# MCU.net
KiCad netlist of a schematic drawn in Altium Designer
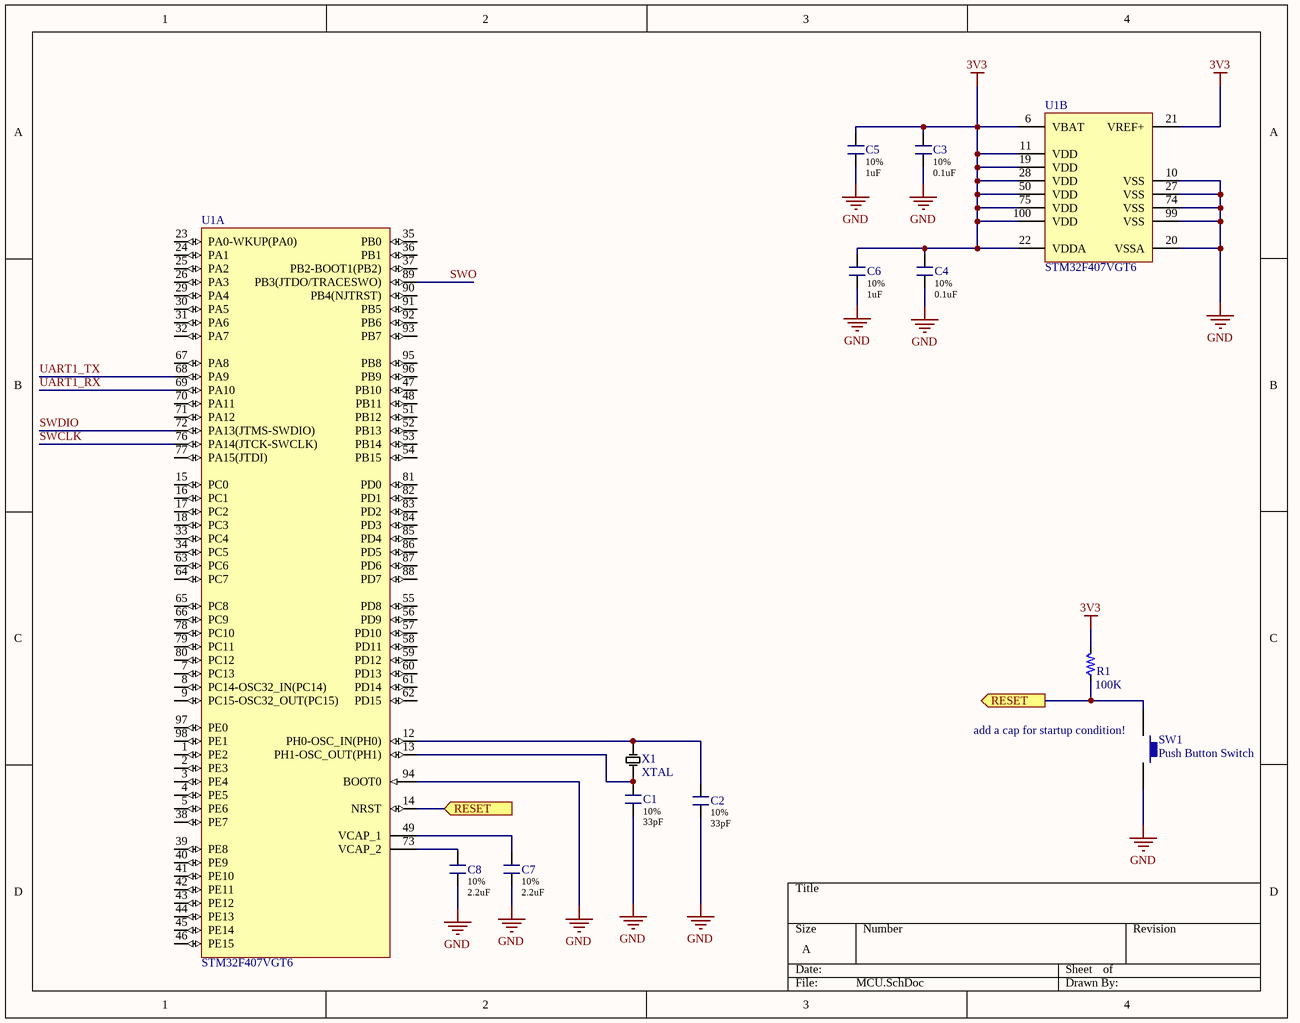
[diagram p0: MCU.SchDoc]

(export (version "E")
  (design (tool "Eeschema 10.0.6"))
  (components
    (comp (ref "C1")
      (value "SCH_GENERIC_CAPACITOR_0603")
      (footprint "PCB_GENERIC_SMD_0603")
      (description "Generic SMD capacitor 0603")
      (fields (field (name "TOLERANCE") "10%") (field (name "CAPACITANCE") "33pF"))
      (libsource (lib "Generic 0603 Capacitor") (part "SCH_GENERIC_CAPACITOR_0603"))
    )
    (comp (ref "C2")
      (value "SCH_GENERIC_CAPACITOR_0603")
      (footprint "PCB_GENERIC_SMD_0603")
      (description "Generic SMD capacitor 0603")
      (fields (field (name "TOLERANCE") "10%") (field (name "CAPACITANCE") "33pF"))
      (libsource (lib "Generic 0603 Capacitor") (part "SCH_GENERIC_CAPACITOR_0603"))
    )
    (comp (ref "C3")
      (value "SCH_GENERIC_CAPACITOR_0603")
      (footprint "PCB_GENERIC_SMD_0603")
      (description "Generic SMD capacitor 0603")
      (fields (field (name "TOLERANCE") "10%") (field (name "CAPACITANCE") "0.1uF"))
      (libsource (lib "Generic 0603 Capacitor") (part "SCH_GENERIC_CAPACITOR_0603"))
    )
    (comp (ref "C4")
      (value "SCH_GENERIC_CAPACITOR_0603")
      (footprint "PCB_GENERIC_SMD_0603")
      (description "Generic SMD capacitor 0603")
      (fields (field (name "TOLERANCE") "10%") (field (name "CAPACITANCE") "0.1uF"))
      (libsource (lib "Generic 0603 Capacitor") (part "SCH_GENERIC_CAPACITOR_0603"))
    )
    (comp (ref "C5")
      (value "SCH_GENERIC_CAPACITOR_0603")
      (footprint "PCB_GENERIC_SMD_0603")
      (description "Generic SMD capacitor 0603")
      (fields (field (name "TOLERANCE") "10%") (field (name "CAPACITANCE") "1uF"))
      (libsource (lib "Generic 0603 Capacitor") (part "SCH_GENERIC_CAPACITOR_0603"))
    )
    (comp (ref "C6")
      (value "SCH_GENERIC_CAPACITOR_0603")
      (footprint "PCB_GENERIC_SMD_0603")
      (description "Generic SMD capacitor 0603")
      (fields (field (name "TOLERANCE") "10%") (field (name "CAPACITANCE") "1uF"))
      (libsource (lib "Generic 0603 Capacitor") (part "SCH_GENERIC_CAPACITOR_0603"))
    )
    (comp (ref "C7")
      (value "SCH_GENERIC_CAPACITOR_0603")
      (footprint "PCB_GENERIC_SMD_0603")
      (description "Generic SMD capacitor 0603")
      (fields (field (name "TOLERANCE") "10%") (field (name "CAPACITANCE") "2.2uF"))
      (libsource (lib "Generic 0603 Capacitor") (part "SCH_GENERIC_CAPACITOR_0603"))
    )
    (comp (ref "C8")
      (value "SCH_GENERIC_CAPACITOR_0603")
      (footprint "PCB_GENERIC_SMD_0603")
      (description "Generic SMD capacitor 0603")
      (fields (field (name "TOLERANCE") "10%") (field (name "CAPACITANCE") "2.2uF"))
      (libsource (lib "Generic 0603 Capacitor") (part "SCH_GENERIC_CAPACITOR_0603"))
    )
    (comp (ref "R1")
      (value "SCH_GENERIC_RESISTOR_0603")
      (footprint "PCB_GENERIC_SMD_0603")
      (description "Generic SMD resistor 0603")
      (fields (field (name "RESISTANCE") "100K"))
      (libsource (lib "Generic 0603 Resistor") (part "SCH_GENERIC_RESISTOR_0603"))
    )
    (comp (ref "SW1")
      (value "Push Button Switch")
      (footprint "Push Button Switch")
      (libsource (lib "Surface Mount Push Button Switch") (part "PushButtonSwitch"))
    )
    (comp (ref "U1")
      (value "STM32F407VGT6")
      (footprint "STM-LQFP100_N")
      (fields (field (name "MANUFACTURER") "STMicroelectronics"))
      (libsource (lib "STMicroelectronics STM32 F4") (part "STM32F407VGT6"))
    )
    (comp (ref "X1")
      (value "XTAL")
      (footprint "CRYSTAL_8MHZ")
      (libsource (lib "Foxslf 8MHz Crystal") (part "Crystal"))
    )
  )
  (nets
    (net (code "1") (name "/RESET") (class "Default")
      (node (ref "R1") (pin "1") (pinfunction "1_1") (pintype "passive"))
      (node (ref "SW1") (pin "1") (pinfunction "1_1") (pintype "passive"))
      (node (ref "U1") (pin "14") (pinfunction "NRST_14") (pintype "bidirectional"))
    )
    (net (code "2") (name "/SWCLK") (class "Default")
      (node (ref "U1") (pin "76") (pinfunction "PA14(JTCK-SWCLK)_76") (pintype "bidirectional"))
    )
    (net (code "3") (name "/SWDIO") (class "Default")
      (node (ref "U1") (pin "72") (pinfunction "PA13(JTMS-SWDIO)_72") (pintype "bidirectional"))
    )
    (net (code "4") (name "/SWO") (class "Default")
      (node (ref "U1") (pin "89") (pinfunction "PB3(JTDO/TRACESWO)_89") (pintype "bidirectional"))
    )
    (net (code "5") (name "/UART1_RX") (class "Default")
      (node (ref "U1") (pin "69") (pinfunction "PA10_69") (pintype "bidirectional"))
    )
    (net (code "6") (name "/UART1_TX") (class "Default")
      (node (ref "U1") (pin "68") (pinfunction "PA9_68") (pintype "bidirectional"))
    )
    (net (code "7") (name "3V3") (class "Default")
      (node (ref "C3") (pin "2") (pinfunction "2_2") (pintype "passive"))
      (node (ref "C4") (pin "2") (pinfunction "2_2") (pintype "passive"))
      (node (ref "C5") (pin "2") (pinfunction "2_2") (pintype "passive"))
      (node (ref "C6") (pin "2") (pinfunction "2_2") (pintype "passive"))
      (node (ref "R1") (pin "2") (pinfunction "2_2") (pintype "passive"))
      (node (ref "U1") (pin "100") (pinfunction "VDD_100") (pintype "power_in"))
      (node (ref "U1") (pin "11") (pinfunction "VDD_11") (pintype "power_in"))
      (node (ref "U1") (pin "19") (pinfunction "VDD_19") (pintype "power_in"))
      (node (ref "U1") (pin "21") (pinfunction "VREF+_21") (pintype "power_in"))
      (node (ref "U1") (pin "22") (pinfunction "VDDA_22") (pintype "power_in"))
      (node (ref "U1") (pin "28") (pinfunction "VDD_28") (pintype "power_in"))
      (node (ref "U1") (pin "50") (pinfunction "VDD_50") (pintype "power_in"))
      (node (ref "U1") (pin "6") (pinfunction "VBAT_6") (pintype "power_in"))
      (node (ref "U1") (pin "75") (pinfunction "VDD_75") (pintype "power_in"))
    )
    (net (code "8") (name "GND") (class "Default")
      (node (ref "C1") (pin "1") (pinfunction "1_1") (pintype "passive"))
      (node (ref "C2") (pin "1") (pinfunction "1_1") (pintype "passive"))
      (node (ref "C3") (pin "1") (pinfunction "1_1") (pintype "passive"))
      (node (ref "C4") (pin "1") (pinfunction "1_1") (pintype "passive"))
      (node (ref "C5") (pin "1") (pinfunction "1_1") (pintype "passive"))
      (node (ref "C6") (pin "1") (pinfunction "1_1") (pintype "passive"))
      (node (ref "C7") (pin "1") (pinfunction "1_1") (pintype "passive"))
      (node (ref "C8") (pin "1") (pinfunction "1_1") (pintype "passive"))
      (node (ref "SW1") (pin "2") (pinfunction "2_2") (pintype "passive"))
      (node (ref "U1") (pin "10") (pinfunction "VSS_10") (pintype "power_in"))
      (node (ref "U1") (pin "20") (pinfunction "VSSA_20") (pintype "power_in"))
      (node (ref "U1") (pin "27") (pinfunction "VSS_27") (pintype "power_in"))
      (node (ref "U1") (pin "74") (pinfunction "VSS_74") (pintype "power_in"))
      (node (ref "U1") (pin "94") (pinfunction "BOOT0_94") (pintype "input"))
      (node (ref "U1") (pin "99") (pinfunction "VSS_99") (pintype "power_in"))
    )
    (net (code "9") (name "Net-(U1A-PH0-OSC_IN(PH0))") (class "Default")
      (node (ref "C2") (pin "2") (pinfunction "2_2") (pintype "passive"))
      (node (ref "U1") (pin "12") (pinfunction "PH0-OSC_IN(PH0)_12") (pintype "bidirectional"))
      (node (ref "X1") (pin "2") (pintype "passive"))
    )
    (net (code "10") (name "Net-(U1A-PH1-OSC_OUT(PH1))") (class "Default")
      (node (ref "C1") (pin "2") (pinfunction "2_2") (pintype "passive"))
      (node (ref "U1") (pin "13") (pinfunction "PH1-OSC_OUT(PH1)_13") (pintype "bidirectional"))
      (node (ref "X1") (pin "1") (pintype "passive"))
    )
    (net (code "11") (name "Net-(U1A-VCAP_1)") (class "Default")
      (node (ref "C7") (pin "2") (pinfunction "2_2") (pintype "passive"))
      (node (ref "U1") (pin "49") (pinfunction "VCAP_1_49") (pintype "power_in"))
    )
    (net (code "12") (name "Net-(U1A-VCAP_2)") (class "Default")
      (node (ref "C8") (pin "2") (pinfunction "2_2") (pintype "passive"))
      (node (ref "U1") (pin "73") (pinfunction "VCAP_2_73") (pintype "power_in"))
    )
    (net (code "13") (name "unconnected-(U1A-PA0-WKUP(PA0)-Pad23)") (class "Default")
      (node (ref "U1") (pin "23") (pinfunction "PA0-WKUP(PA0)_23") (pintype "bidirectional"))
    )
    (net (code "14") (name "unconnected-(U1A-PA1-Pad24)") (class "Default")
      (node (ref "U1") (pin "24") (pinfunction "PA1_24") (pintype "bidirectional"))
    )
    (net (code "15") (name "unconnected-(U1A-PA2-Pad25)") (class "Default")
      (node (ref "U1") (pin "25") (pinfunction "PA2_25") (pintype "bidirectional"))
    )
    (net (code "16") (name "unconnected-(U1A-PA3-Pad26)") (class "Default")
      (node (ref "U1") (pin "26") (pinfunction "PA3_26") (pintype "bidirectional"))
    )
    (net (code "17") (name "unconnected-(U1A-PA4-Pad29)") (class "Default")
      (node (ref "U1") (pin "29") (pinfunction "PA4_29") (pintype "bidirectional"))
    )
    (net (code "18") (name "unconnected-(U1A-PA5-Pad30)") (class "Default")
      (node (ref "U1") (pin "30") (pinfunction "PA5_30") (pintype "bidirectional"))
    )
    (net (code "19") (name "unconnected-(U1A-PA6-Pad31)") (class "Default")
      (node (ref "U1") (pin "31") (pinfunction "PA6_31") (pintype "bidirectional"))
    )
    (net (code "20") (name "unconnected-(U1A-PA7-Pad32)") (class "Default")
      (node (ref "U1") (pin "32") (pinfunction "PA7_32") (pintype "bidirectional"))
    )
    (net (code "21") (name "unconnected-(U1A-PA8-Pad67)") (class "Default")
      (node (ref "U1") (pin "67") (pinfunction "PA8_67") (pintype "bidirectional"))
    )
    (net (code "22") (name "unconnected-(U1A-PA11-Pad70)") (class "Default")
      (node (ref "U1") (pin "70") (pinfunction "PA11_70") (pintype "bidirectional"))
    )
    (net (code "23") (name "unconnected-(U1A-PA12-Pad71)") (class "Default")
      (node (ref "U1") (pin "71") (pinfunction "PA12_71") (pintype "bidirectional"))
    )
    (net (code "24") (name "unconnected-(U1A-PA15(JTDI)-Pad77)") (class "Default")
      (node (ref "U1") (pin "77") (pinfunction "PA15(JTDI)_77") (pintype "bidirectional"))
    )
    (net (code "25") (name "unconnected-(U1A-PB0-Pad35)") (class "Default")
      (node (ref "U1") (pin "35") (pinfunction "PB0_35") (pintype "bidirectional"))
    )
    (net (code "26") (name "unconnected-(U1A-PB1-Pad36)") (class "Default")
      (node (ref "U1") (pin "36") (pinfunction "PB1_36") (pintype "bidirectional"))
    )
    (net (code "27") (name "unconnected-(U1A-PB2-BOOT1(PB2)-Pad37)") (class "Default")
      (node (ref "U1") (pin "37") (pinfunction "PB2-BOOT1(PB2)_37") (pintype "bidirectional"))
    )
    (net (code "28") (name "unconnected-(U1A-PB4(NJTRST)-Pad90)") (class "Default")
      (node (ref "U1") (pin "90") (pinfunction "PB4(NJTRST)_90") (pintype "bidirectional"))
    )
    (net (code "29") (name "unconnected-(U1A-PB5-Pad91)") (class "Default")
      (node (ref "U1") (pin "91") (pinfunction "PB5_91") (pintype "bidirectional"))
    )
    (net (code "30") (name "unconnected-(U1A-PB6-Pad92)") (class "Default")
      (node (ref "U1") (pin "92") (pinfunction "PB6_92") (pintype "bidirectional"))
    )
    (net (code "31") (name "unconnected-(U1A-PB7-Pad93)") (class "Default")
      (node (ref "U1") (pin "93") (pinfunction "PB7_93") (pintype "bidirectional"))
    )
    (net (code "32") (name "unconnected-(U1A-PB8-Pad95)") (class "Default")
      (node (ref "U1") (pin "95") (pinfunction "PB8_95") (pintype "bidirectional"))
    )
    (net (code "33") (name "unconnected-(U1A-PB9-Pad96)") (class "Default")
      (node (ref "U1") (pin "96") (pinfunction "PB9_96") (pintype "bidirectional"))
    )
    (net (code "34") (name "unconnected-(U1A-PB10-Pad47)") (class "Default")
      (node (ref "U1") (pin "47") (pinfunction "PB10_47") (pintype "bidirectional"))
    )
    (net (code "35") (name "unconnected-(U1A-PB11-Pad48)") (class "Default")
      (node (ref "U1") (pin "48") (pinfunction "PB11_48") (pintype "bidirectional"))
    )
    (net (code "36") (name "unconnected-(U1A-PB12-Pad51)") (class "Default")
      (node (ref "U1") (pin "51") (pinfunction "PB12_51") (pintype "bidirectional"))
    )
    (net (code "37") (name "unconnected-(U1A-PB13-Pad52)") (class "Default")
      (node (ref "U1") (pin "52") (pinfunction "PB13_52") (pintype "bidirectional"))
    )
    (net (code "38") (name "unconnected-(U1A-PB14-Pad53)") (class "Default")
      (node (ref "U1") (pin "53") (pinfunction "PB14_53") (pintype "bidirectional"))
    )
    (net (code "39") (name "unconnected-(U1A-PB15-Pad54)") (class "Default")
      (node (ref "U1") (pin "54") (pinfunction "PB15_54") (pintype "bidirectional"))
    )
    (net (code "40") (name "unconnected-(U1A-PC0-Pad15)") (class "Default")
      (node (ref "U1") (pin "15") (pinfunction "PC0_15") (pintype "bidirectional"))
    )
    (net (code "41") (name "unconnected-(U1A-PC1-Pad16)") (class "Default")
      (node (ref "U1") (pin "16") (pinfunction "PC1_16") (pintype "bidirectional"))
    )
    (net (code "42") (name "unconnected-(U1A-PC2-Pad17)") (class "Default")
      (node (ref "U1") (pin "17") (pinfunction "PC2_17") (pintype "bidirectional"))
    )
    (net (code "43") (name "unconnected-(U1A-PC3-Pad18)") (class "Default")
      (node (ref "U1") (pin "18") (pinfunction "PC3_18") (pintype "bidirectional"))
    )
    (net (code "44") (name "unconnected-(U1A-PC4-Pad33)") (class "Default")
      (node (ref "U1") (pin "33") (pinfunction "PC4_33") (pintype "bidirectional"))
    )
    (net (code "45") (name "unconnected-(U1A-PC5-Pad34)") (class "Default")
      (node (ref "U1") (pin "34") (pinfunction "PC5_34") (pintype "bidirectional"))
    )
    (net (code "46") (name "unconnected-(U1A-PC6-Pad63)") (class "Default")
      (node (ref "U1") (pin "63") (pinfunction "PC6_63") (pintype "bidirectional"))
    )
    (net (code "47") (name "unconnected-(U1A-PC7-Pad64)") (class "Default")
      (node (ref "U1") (pin "64") (pinfunction "PC7_64") (pintype "bidirectional"))
    )
    (net (code "48") (name "unconnected-(U1A-PC8-Pad65)") (class "Default")
      (node (ref "U1") (pin "65") (pinfunction "PC8_65") (pintype "bidirectional"))
    )
    (net (code "49") (name "unconnected-(U1A-PC9-Pad66)") (class "Default")
      (node (ref "U1") (pin "66") (pinfunction "PC9_66") (pintype "bidirectional"))
    )
    (net (code "50") (name "unconnected-(U1A-PC10-Pad78)") (class "Default")
      (node (ref "U1") (pin "78") (pinfunction "PC10_78") (pintype "bidirectional"))
    )
    (net (code "51") (name "unconnected-(U1A-PC11-Pad79)") (class "Default")
      (node (ref "U1") (pin "79") (pinfunction "PC11_79") (pintype "bidirectional"))
    )
    (net (code "52") (name "unconnected-(U1A-PC12-Pad80)") (class "Default")
      (node (ref "U1") (pin "80") (pinfunction "PC12_80") (pintype "bidirectional"))
    )
    (net (code "53") (name "unconnected-(U1A-PC13-Pad7)") (class "Default")
      (node (ref "U1") (pin "7") (pinfunction "PC13_7") (pintype "bidirectional"))
    )
    (net (code "54") (name "unconnected-(U1A-PC14-OSC32_IN(PC14)-Pad8)") (class "Default")
      (node (ref "U1") (pin "8") (pinfunction "PC14-OSC32_IN(PC14)_8") (pintype "bidirectional"))
    )
    (net (code "55") (name "unconnected-(U1A-PC15-OSC32_OUT(PC15)-Pad9)") (class "Default")
      (node (ref "U1") (pin "9") (pinfunction "PC15-OSC32_OUT(PC15)_9") (pintype "bidirectional"))
    )
    (net (code "56") (name "unconnected-(U1A-PD0-Pad81)") (class "Default")
      (node (ref "U1") (pin "81") (pinfunction "PD0_81") (pintype "bidirectional"))
    )
    (net (code "57") (name "unconnected-(U1A-PD1-Pad82)") (class "Default")
      (node (ref "U1") (pin "82") (pinfunction "PD1_82") (pintype "bidirectional"))
    )
    (net (code "58") (name "unconnected-(U1A-PD2-Pad83)") (class "Default")
      (node (ref "U1") (pin "83") (pinfunction "PD2_83") (pintype "bidirectional"))
    )
    (net (code "59") (name "unconnected-(U1A-PD3-Pad84)") (class "Default")
      (node (ref "U1") (pin "84") (pinfunction "PD3_84") (pintype "bidirectional"))
    )
    (net (code "60") (name "unconnected-(U1A-PD4-Pad85)") (class "Default")
      (node (ref "U1") (pin "85") (pinfunction "PD4_85") (pintype "bidirectional"))
    )
    (net (code "61") (name "unconnected-(U1A-PD5-Pad86)") (class "Default")
      (node (ref "U1") (pin "86") (pinfunction "PD5_86") (pintype "bidirectional"))
    )
    (net (code "62") (name "unconnected-(U1A-PD6-Pad87)") (class "Default")
      (node (ref "U1") (pin "87") (pinfunction "PD6_87") (pintype "bidirectional"))
    )
    (net (code "63") (name "unconnected-(U1A-PD7-Pad88)") (class "Default")
      (node (ref "U1") (pin "88") (pinfunction "PD7_88") (pintype "bidirectional"))
    )
    (net (code "64") (name "unconnected-(U1A-PD8-Pad55)") (class "Default")
      (node (ref "U1") (pin "55") (pinfunction "PD8_55") (pintype "bidirectional"))
    )
    (net (code "65") (name "unconnected-(U1A-PD9-Pad56)") (class "Default")
      (node (ref "U1") (pin "56") (pinfunction "PD9_56") (pintype "bidirectional"))
    )
    (net (code "66") (name "unconnected-(U1A-PD10-Pad57)") (class "Default")
      (node (ref "U1") (pin "57") (pinfunction "PD10_57") (pintype "bidirectional"))
    )
    (net (code "67") (name "unconnected-(U1A-PD11-Pad58)") (class "Default")
      (node (ref "U1") (pin "58") (pinfunction "PD11_58") (pintype "bidirectional"))
    )
    (net (code "68") (name "unconnected-(U1A-PD12-Pad59)") (class "Default")
      (node (ref "U1") (pin "59") (pinfunction "PD12_59") (pintype "bidirectional"))
    )
    (net (code "69") (name "unconnected-(U1A-PD13-Pad60)") (class "Default")
      (node (ref "U1") (pin "60") (pinfunction "PD13_60") (pintype "bidirectional"))
    )
    (net (code "70") (name "unconnected-(U1A-PD14-Pad61)") (class "Default")
      (node (ref "U1") (pin "61") (pinfunction "PD14_61") (pintype "bidirectional"))
    )
    (net (code "71") (name "unconnected-(U1A-PD15-Pad62)") (class "Default")
      (node (ref "U1") (pin "62") (pinfunction "PD15_62") (pintype "bidirectional"))
    )
    (net (code "72") (name "unconnected-(U1A-PE0-Pad97)") (class "Default")
      (node (ref "U1") (pin "97") (pinfunction "PE0_97") (pintype "bidirectional"))
    )
    (net (code "73") (name "unconnected-(U1A-PE1-Pad98)") (class "Default")
      (node (ref "U1") (pin "98") (pinfunction "PE1_98") (pintype "bidirectional"))
    )
    (net (code "74") (name "unconnected-(U1A-PE2-Pad1)") (class "Default")
      (node (ref "U1") (pin "1") (pinfunction "PE2_1") (pintype "bidirectional"))
    )
    (net (code "75") (name "unconnected-(U1A-PE3-Pad2)") (class "Default")
      (node (ref "U1") (pin "2") (pinfunction "PE3_2") (pintype "bidirectional"))
    )
    (net (code "76") (name "unconnected-(U1A-PE4-Pad3)") (class "Default")
      (node (ref "U1") (pin "3") (pinfunction "PE4_3") (pintype "bidirectional"))
    )
    (net (code "77") (name "unconnected-(U1A-PE5-Pad4)") (class "Default")
      (node (ref "U1") (pin "4") (pinfunction "PE5_4") (pintype "bidirectional"))
    )
    (net (code "78") (name "unconnected-(U1A-PE6-Pad5)") (class "Default")
      (node (ref "U1") (pin "5") (pinfunction "PE6_5") (pintype "bidirectional"))
    )
    (net (code "79") (name "unconnected-(U1A-PE7-Pad38)") (class "Default")
      (node (ref "U1") (pin "38") (pinfunction "PE7_38") (pintype "bidirectional"))
    )
    (net (code "80") (name "unconnected-(U1A-PE8-Pad39)") (class "Default")
      (node (ref "U1") (pin "39") (pinfunction "PE8_39") (pintype "bidirectional"))
    )
    (net (code "81") (name "unconnected-(U1A-PE9-Pad40)") (class "Default")
      (node (ref "U1") (pin "40") (pinfunction "PE9_40") (pintype "bidirectional"))
    )
    (net (code "82") (name "unconnected-(U1A-PE10-Pad41)") (class "Default")
      (node (ref "U1") (pin "41") (pinfunction "PE10_41") (pintype "bidirectional"))
    )
    (net (code "83") (name "unconnected-(U1A-PE11-Pad42)") (class "Default")
      (node (ref "U1") (pin "42") (pinfunction "PE11_42") (pintype "bidirectional"))
    )
    (net (code "84") (name "unconnected-(U1A-PE12-Pad43)") (class "Default")
      (node (ref "U1") (pin "43") (pinfunction "PE12_43") (pintype "bidirectional"))
    )
    (net (code "85") (name "unconnected-(U1A-PE13-Pad44)") (class "Default")
      (node (ref "U1") (pin "44") (pinfunction "PE13_44") (pintype "bidirectional"))
    )
    (net (code "86") (name "unconnected-(U1A-PE14-Pad45)") (class "Default")
      (node (ref "U1") (pin "45") (pinfunction "PE14_45") (pintype "bidirectional"))
    )
    (net (code "87") (name "unconnected-(U1A-PE15-Pad46)") (class "Default")
      (node (ref "U1") (pin "46") (pinfunction "PE15_46") (pintype "bidirectional"))
    )
  )
)
